# counter_test.net
KiCad netlist of a schematic drawn in EAGLE
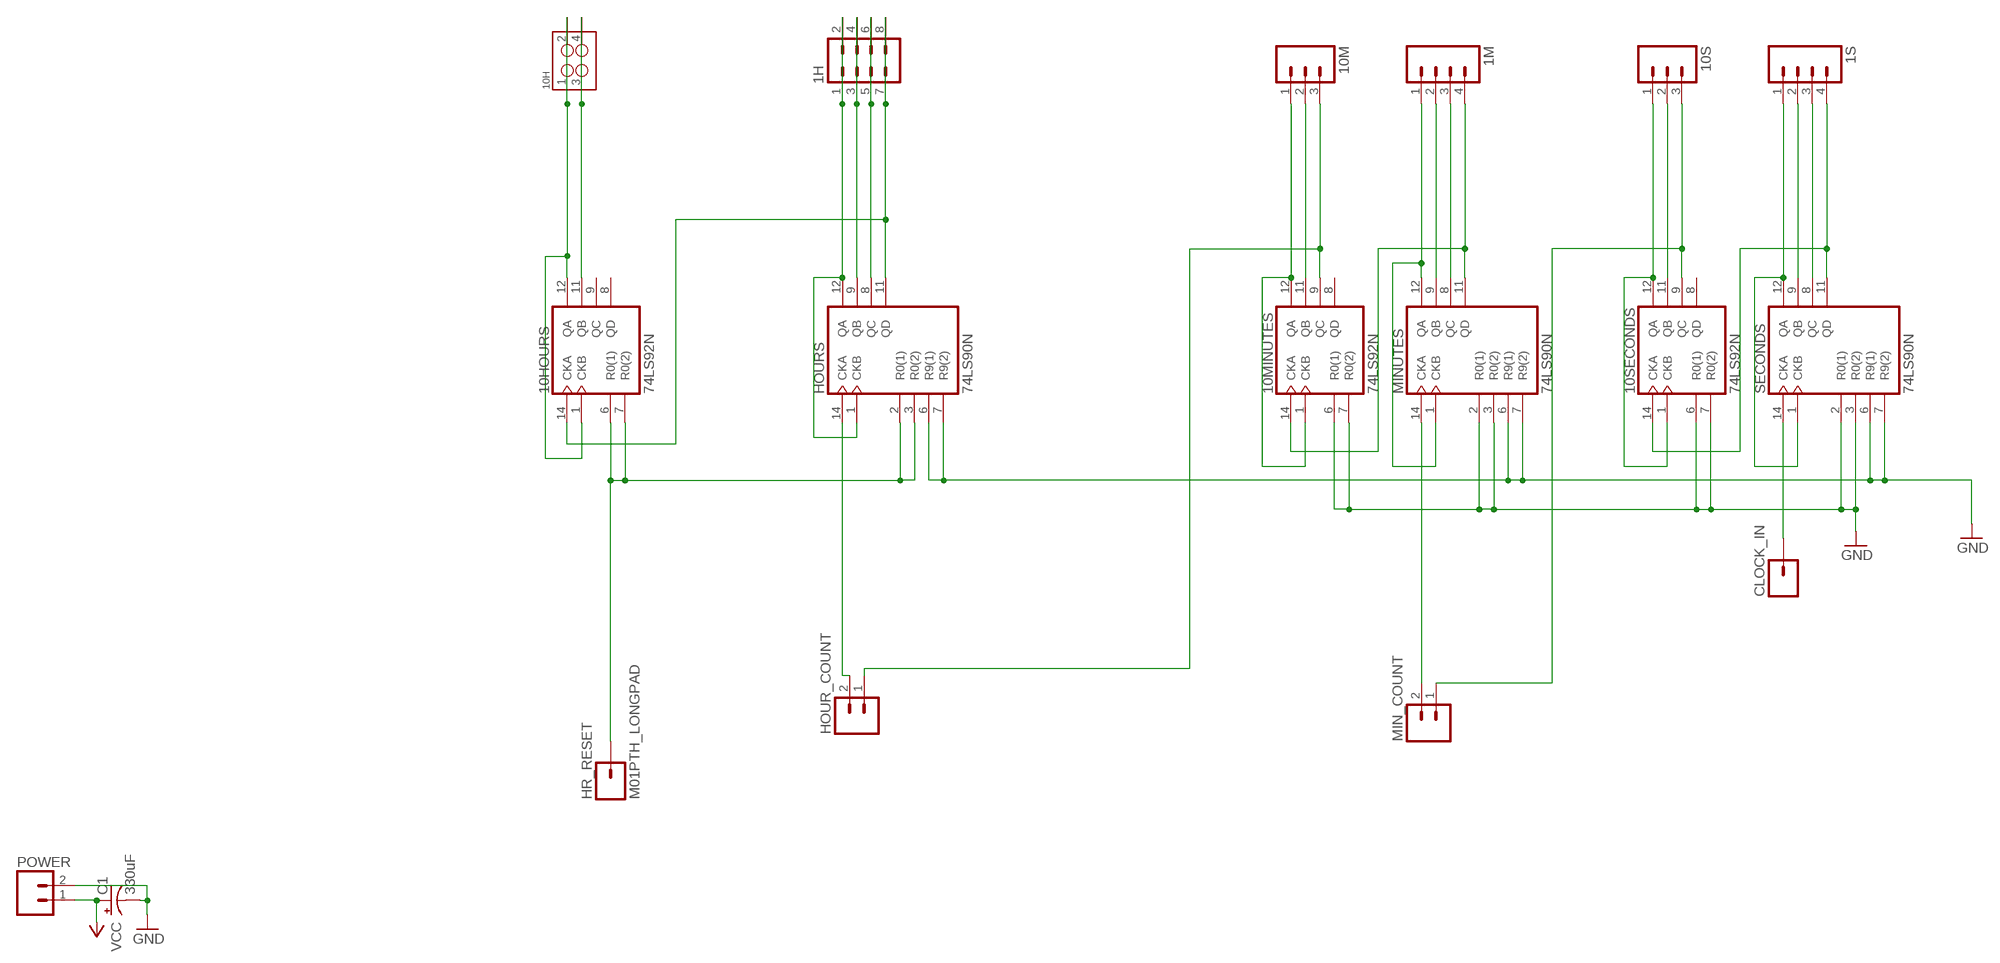
[diagram p0: schematic, sheet 1]

(export (version "E")
  (design (tool "Eeschema 10.0.6"))
  (components
    (comp (ref "1H")
      (value "M04X2")
      (footprint "eagle-import:2X4")
      (libsource (lib "eagle-import") (part "M04X2"))
    )
    (comp (ref "1M")
      (value "M04LONGPADS")
      (footprint "eagle-import:1X04_LONGPADS")
      (libsource (lib "eagle-import") (part "M04LONGPADS"))
    )
    (comp (ref "1S")
      (value "M04LONGPADS")
      (footprint "eagle-import:1X04_LONGPADS")
      (libsource (lib "eagle-import") (part "M04LONGPADS"))
    )
    (comp (ref "10H")
      (value "M02X2")
      (footprint "eagle-import:2X2")
      (libsource (lib "eagle-import") (part "M02X2"))
    )
    (comp (ref "10HOURS")
      (value "74LS92N")
      (footprint "eagle-import:DIL14")
      (libsource (lib "eagle-import") (part "7492NLS"))
    )
    (comp (ref "10M")
      (value "M03LONGPADS")
      (footprint "eagle-import:1X03_LONGPADS")
      (libsource (lib "eagle-import") (part "M03LONGPADS"))
    )
    (comp (ref "10MINUTES")
      (value "74LS92N")
      (footprint "eagle-import:DIL14")
      (libsource (lib "eagle-import") (part "7492NLS"))
    )
    (comp (ref "10S")
      (value "M03LONGPADS")
      (footprint "eagle-import:1X03_LONGPADS")
      (libsource (lib "eagle-import") (part "M03LONGPADS"))
    )
    (comp (ref "10SECONDS")
      (value "74LS92N")
      (footprint "eagle-import:DIL14")
      (libsource (lib "eagle-import") (part "7492NLS"))
    )
    (comp (ref "C1")
      (value "330uF")
      (footprint "eagle-import:E3,5-8")
      (libsource (lib "eagle-import") (part "CAPACITOR_POLE3.5-8"))
    )
    (comp (ref "CLOCK_IN")
      (value "M01PTH_LONGPAD")
      (footprint "eagle-import:1X01_LONGPAD")
      (libsource (lib "eagle-import") (part "M01PTH_LONGPAD"))
    )
    (comp (ref "HOURS")
      (value "74LS90N")
      (footprint "eagle-import:DIL14")
      (libsource (lib "eagle-import") (part "7490NLS"))
    )
    (comp (ref "HOUR_COUNT")
      (value "M02PTH3")
      (footprint "eagle-import:1X02_LONGPADS")
      (libsource (lib "eagle-import") (part "M02PTH3"))
    )
    (comp (ref "HR_RESET")
      (value "M01PTH_LONGPAD")
      (footprint "eagle-import:1X01_LONGPAD")
      (libsource (lib "eagle-import") (part "M01PTH_LONGPAD"))
    )
    (comp (ref "MINUTES")
      (value "74LS90N")
      (footprint "eagle-import:DIL14")
      (libsource (lib "eagle-import") (part "7490NLS"))
    )
    (comp (ref "MIN_COUNT")
      (value "M02PTH3")
      (footprint "eagle-import:1X02_LONGPADS")
      (libsource (lib "eagle-import") (part "M02PTH3"))
    )
    (comp (ref "POWER")
      (value "M02PTH3")
      (footprint "eagle-import:1X02_LONGPADS")
      (libsource (lib "eagle-import") (part "M02PTH3"))
    )
    (comp (ref "SECONDS")
      (value "74LS90N")
      (footprint "eagle-import:DIL14")
      (libsource (lib "eagle-import") (part "7490NLS"))
    )
  )
  (nets
    (net (code "1") (name "GND") (class "Default")
      (node (ref "10MINUTES") (pin "6") (pinfunction "R0(1)_6") (pintype "input"))
      (node (ref "10MINUTES") (pin "7") (pinfunction "R0(2)_7") (pintype "input"))
      (node (ref "10SECONDS") (pin "6") (pinfunction "R0(1)_6") (pintype "input"))
      (node (ref "10SECONDS") (pin "7") (pinfunction "R0(2)_7") (pintype "input"))
      (node (ref "C1") (pin "-") (pinfunction "-_-") (pintype "passive"))
      (node (ref "HOURS") (pin "6") (pinfunction "R9(1)_6") (pintype "input"))
      (node (ref "HOURS") (pin "7") (pinfunction "R9(2)_7") (pintype "input"))
      (node (ref "MINUTES") (pin "2") (pinfunction "R0(1)_2") (pintype "input"))
      (node (ref "MINUTES") (pin "3") (pinfunction "R0(2)_3") (pintype "input"))
      (node (ref "MINUTES") (pin "6") (pinfunction "R9(1)_6") (pintype "input"))
      (node (ref "MINUTES") (pin "7") (pinfunction "R9(2)_7") (pintype "input"))
      (node (ref "POWER") (pin "2") (pinfunction "2_2") (pintype "passive"))
      (node (ref "SECONDS") (pin "2") (pinfunction "R0(1)_2") (pintype "input"))
      (node (ref "SECONDS") (pin "3") (pinfunction "R0(2)_3") (pintype "input"))
      (node (ref "SECONDS") (pin "6") (pinfunction "R9(1)_6") (pintype "input"))
      (node (ref "SECONDS") (pin "7") (pinfunction "R9(2)_7") (pintype "input"))
    )
    (net (code "2") (name "Net-(10HOURSA-CKA)") (class "Default")
      (node (ref "10HOURS") (pin "14") (pinfunction "CKA_14") (pintype "input"))
      (node (ref "1H") (pin "7") (pinfunction "7_7") (pintype "passive"))
      (node (ref "1H") (pin "8") (pinfunction "8_8") (pintype "passive"))
      (node (ref "HOURS") (pin "11") (pinfunction "QD_11") (pintype "output"))
    )
    (net (code "3") (name "Net-(10HOURSA-CKB)") (class "Default")
      (node (ref "10H") (pin "1") (pinfunction "1_1") (pintype "bidirectional"))
      (node (ref "10H") (pin "2") (pinfunction "2_2") (pintype "bidirectional"))
      (node (ref "10HOURS") (pin "1") (pinfunction "CKB_1") (pintype "input"))
      (node (ref "10HOURS") (pin "12") (pinfunction "QA_12") (pintype "output"))
    )
    (net (code "4") (name "Net-(10HOURSA-QB)") (class "Default")
      (node (ref "10H") (pin "3") (pinfunction "3_3") (pintype "bidirectional"))
      (node (ref "10H") (pin "4") (pinfunction "4_4") (pintype "bidirectional"))
      (node (ref "10HOURS") (pin "11") (pinfunction "QB_11") (pintype "output"))
    )
    (net (code "5") (name "Net-(10HOURSA-R0(1))") (class "Default")
      (node (ref "10HOURS") (pin "6") (pinfunction "R0(1)_6") (pintype "input"))
      (node (ref "10HOURS") (pin "7") (pinfunction "R0(2)_7") (pintype "input"))
      (node (ref "HOURS") (pin "2") (pinfunction "R0(1)_2") (pintype "input"))
      (node (ref "HOURS") (pin "3") (pinfunction "R0(2)_3") (pintype "input"))
      (node (ref "HR_RESET") (pin "1") (pinfunction "1_1") (pintype "passive"))
    )
    (net (code "6") (name "Net-(10MINUTESA-CKA)") (class "Default")
      (node (ref "10MINUTES") (pin "14") (pinfunction "CKA_14") (pintype "input"))
      (node (ref "1M") (pin "4") (pinfunction "4_4") (pintype "passive"))
      (node (ref "MINUTES") (pin "11") (pinfunction "QD_11") (pintype "output"))
    )
    (net (code "7") (name "Net-(10MINUTESA-CKB)") (class "Default")
      (node (ref "10M") (pin "1") (pinfunction "1_1") (pintype "passive"))
      (node (ref "10MINUTES") (pin "1") (pinfunction "CKB_1") (pintype "input"))
      (node (ref "10MINUTES") (pin "12") (pinfunction "QA_12") (pintype "output"))
    )
    (net (code "8") (name "Net-(10MINUTESA-QB)") (class "Default")
      (node (ref "10M") (pin "2") (pinfunction "2_2") (pintype "passive"))
      (node (ref "10MINUTES") (pin "11") (pinfunction "QB_11") (pintype "output"))
    )
    (net (code "9") (name "Net-(10MINUTESA-QC)") (class "Default")
      (node (ref "10M") (pin "3") (pinfunction "3_3") (pintype "passive"))
      (node (ref "10MINUTES") (pin "9") (pinfunction "QC_9") (pintype "output"))
      (node (ref "HOUR_COUNT") (pin "1") (pinfunction "1_1") (pintype "passive"))
    )
    (net (code "10") (name "Net-(10SECONDSA-CKA)") (class "Default")
      (node (ref "10SECONDS") (pin "14") (pinfunction "CKA_14") (pintype "input"))
      (node (ref "1S") (pin "4") (pinfunction "4_4") (pintype "passive"))
      (node (ref "SECONDS") (pin "11") (pinfunction "QD_11") (pintype "output"))
    )
    (net (code "11") (name "Net-(10SECONDSA-CKB)") (class "Default")
      (node (ref "10S") (pin "1") (pinfunction "1_1") (pintype "passive"))
      (node (ref "10SECONDS") (pin "1") (pinfunction "CKB_1") (pintype "input"))
      (node (ref "10SECONDS") (pin "12") (pinfunction "QA_12") (pintype "output"))
    )
    (net (code "12") (name "Net-(10SECONDSA-QB)") (class "Default")
      (node (ref "10S") (pin "2") (pinfunction "2_2") (pintype "passive"))
      (node (ref "10SECONDS") (pin "11") (pinfunction "QB_11") (pintype "output"))
    )
    (net (code "13") (name "Net-(10SECONDSA-QC)") (class "Default")
      (node (ref "10S") (pin "3") (pinfunction "3_3") (pintype "passive"))
      (node (ref "10SECONDS") (pin "9") (pinfunction "QC_9") (pintype "output"))
      (node (ref "MIN_COUNT") (pin "1") (pinfunction "1_1") (pintype "passive"))
    )
    (net (code "14") (name "Net-(HOURSA-CKA)") (class "Default")
      (node (ref "HOURS") (pin "14") (pinfunction "CKA_14") (pintype "input"))
      (node (ref "HOUR_COUNT") (pin "2") (pinfunction "2_2") (pintype "passive"))
    )
    (net (code "15") (name "Net-(HOURSA-CKB)") (class "Default")
      (node (ref "1H") (pin "1") (pinfunction "1_1") (pintype "passive"))
      (node (ref "1H") (pin "2") (pinfunction "2_2") (pintype "passive"))
      (node (ref "HOURS") (pin "1") (pinfunction "CKB_1") (pintype "input"))
      (node (ref "HOURS") (pin "12") (pinfunction "QA_12") (pintype "output"))
    )
    (net (code "16") (name "Net-(HOURSA-QB)") (class "Default")
      (node (ref "1H") (pin "3") (pinfunction "3_3") (pintype "passive"))
      (node (ref "1H") (pin "4") (pinfunction "4_4") (pintype "passive"))
      (node (ref "HOURS") (pin "9") (pinfunction "QB_9") (pintype "output"))
    )
    (net (code "17") (name "Net-(HOURSA-QC)") (class "Default")
      (node (ref "1H") (pin "5") (pinfunction "5_5") (pintype "passive"))
      (node (ref "1H") (pin "6") (pinfunction "6_6") (pintype "passive"))
      (node (ref "HOURS") (pin "8") (pinfunction "QC_8") (pintype "output"))
    )
    (net (code "18") (name "Net-(MINUTESA-CKA)") (class "Default")
      (node (ref "MINUTES") (pin "14") (pinfunction "CKA_14") (pintype "input"))
      (node (ref "MIN_COUNT") (pin "2") (pinfunction "2_2") (pintype "passive"))
    )
    (net (code "19") (name "Net-(MINUTESA-CKB)") (class "Default")
      (node (ref "1M") (pin "1") (pinfunction "1_1") (pintype "passive"))
      (node (ref "MINUTES") (pin "1") (pinfunction "CKB_1") (pintype "input"))
      (node (ref "MINUTES") (pin "12") (pinfunction "QA_12") (pintype "output"))
    )
    (net (code "20") (name "Net-(MINUTESA-QB)") (class "Default")
      (node (ref "1M") (pin "2") (pinfunction "2_2") (pintype "passive"))
      (node (ref "MINUTES") (pin "9") (pinfunction "QB_9") (pintype "output"))
    )
    (net (code "21") (name "Net-(MINUTESA-QC)") (class "Default")
      (node (ref "1M") (pin "3") (pinfunction "3_3") (pintype "passive"))
      (node (ref "MINUTES") (pin "8") (pinfunction "QC_8") (pintype "output"))
    )
    (net (code "22") (name "Net-(SECONDSA-CKA)") (class "Default")
      (node (ref "CLOCK_IN") (pin "1") (pinfunction "1_1") (pintype "passive"))
      (node (ref "SECONDS") (pin "14") (pinfunction "CKA_14") (pintype "input"))
    )
    (net (code "23") (name "Net-(SECONDSA-CKB)") (class "Default")
      (node (ref "1S") (pin "1") (pinfunction "1_1") (pintype "passive"))
      (node (ref "SECONDS") (pin "1") (pinfunction "CKB_1") (pintype "input"))
      (node (ref "SECONDS") (pin "12") (pinfunction "QA_12") (pintype "output"))
    )
    (net (code "24") (name "Net-(SECONDSA-QB)") (class "Default")
      (node (ref "1S") (pin "2") (pinfunction "2_2") (pintype "passive"))
      (node (ref "SECONDS") (pin "9") (pinfunction "QB_9") (pintype "output"))
    )
    (net (code "25") (name "Net-(SECONDSA-QC)") (class "Default")
      (node (ref "1S") (pin "3") (pinfunction "3_3") (pintype "passive"))
      (node (ref "SECONDS") (pin "8") (pinfunction "QC_8") (pintype "output"))
    )
    (net (code "26") (name "VCC") (class "Default")
      (node (ref "C1") (pin "+") (pinfunction "+_+") (pintype "passive"))
      (node (ref "POWER") (pin "1") (pinfunction "1_1") (pintype "passive"))
    )
    (net (code "27") (name "unconnected-(10HOURSA-QC-Pad9)") (class "Default")
      (node (ref "10HOURS") (pin "9") (pinfunction "QC_9") (pintype "output"))
    )
    (net (code "28") (name "unconnected-(10HOURSA-QD-Pad8)") (class "Default")
      (node (ref "10HOURS") (pin "8") (pinfunction "QD_8") (pintype "output"))
    )
    (net (code "29") (name "unconnected-(10MINUTESA-QD-Pad8)") (class "Default")
      (node (ref "10MINUTES") (pin "8") (pinfunction "QD_8") (pintype "output"))
    )
    (net (code "30") (name "unconnected-(10SECONDSA-QD-Pad8)") (class "Default")
      (node (ref "10SECONDS") (pin "8") (pinfunction "QD_8") (pintype "output"))
    )
  )
)
